# ATtiny84.net
KiCad netlist of a schematic drawn in EAGLE
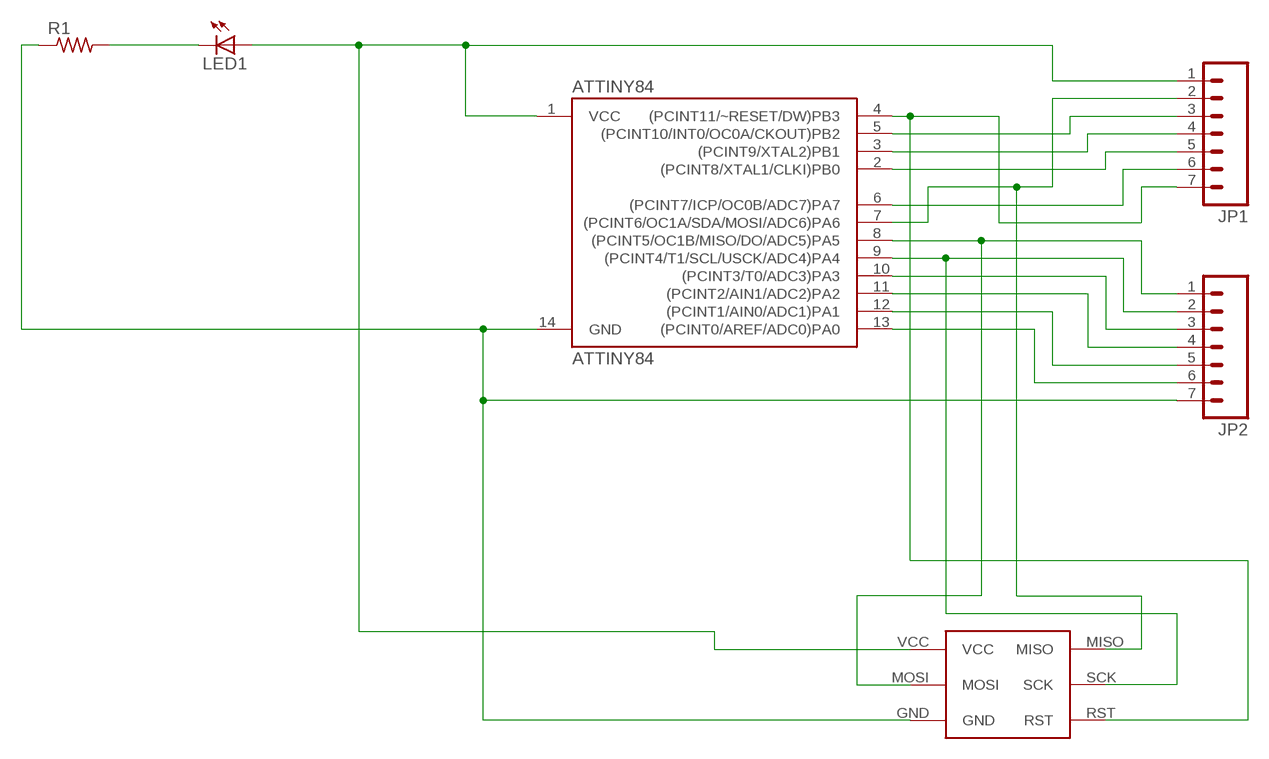
[diagram p0: schematic, sheet 1]

(export (version "E")
  (design (tool "Eeschema 10.0.6"))
  (components
    (comp (ref "ATTINY84")
      (value "ATTINY84")
      (footprint "eagle-import:SO14")
      (libsource (lib "eagle-import") (part "ATTINY84"))
    )
    (comp (ref "JP1")
      (value "M07")
      (footprint "eagle-import:1X07")
      (libsource (lib "eagle-import") (part "M07"))
    )
    (comp (ref "JP2")
      (value "M07")
      (footprint "eagle-import:1X07")
      (libsource (lib "eagle-import") (part "M07"))
    )
    (comp (ref "LED1")
      (value "LEDSML0603")
      (footprint "eagle-import:SML0603")
      (libsource (lib "eagle-import") (part "LEDSML0603"))
    )
    (comp (ref "R1")
      (value "R-US_R0805W")
      (footprint "eagle-import:R0805W")
      (libsource (lib "eagle-import") (part "R-US_R0805W"))
    )
    (comp (ref "U$2")
      (value "POGO_PIN_SPI_PAD")
      (footprint "eagle-import:POGO_PIN_SPI_PAD")
      (libsource (lib "eagle-import") (part "POGO_PIN_SPI_PAD"))
    )
  )
  (nets
    (net (code "1") (name "Net-(ATTINY84-(PCINT0{slash}AREF{slash}ADC0)PA0)") (class "Default")
      (node (ref "ATTINY84") (pin "13") (pinfunction "(PCINT0/AREF/ADC0)PA0_13") (pintype "bidirectional"))
      (node (ref "JP2") (pin "6") (pinfunction "6_6") (pintype "passive"))
    )
    (net (code "2") (name "Net-(ATTINY84-(PCINT1{slash}AIN0{slash}ADC1)PA1)") (class "Default")
      (node (ref "ATTINY84") (pin "12") (pinfunction "(PCINT1/AIN0/ADC1)PA1_12") (pintype "bidirectional"))
      (node (ref "JP2") (pin "5") (pinfunction "5_5") (pintype "passive"))
    )
    (net (code "3") (name "Net-(ATTINY84-(PCINT2{slash}AIN1{slash}ADC2)PA2)") (class "Default")
      (node (ref "ATTINY84") (pin "11") (pinfunction "(PCINT2/AIN1/ADC2)PA2_11") (pintype "bidirectional"))
      (node (ref "JP2") (pin "4") (pinfunction "4_4") (pintype "passive"))
    )
    (net (code "4") (name "Net-(ATTINY84-(PCINT3{slash}T0{slash}ADC3)PA3)") (class "Default")
      (node (ref "ATTINY84") (pin "10") (pinfunction "(PCINT3/T0/ADC3)PA3_10") (pintype "bidirectional"))
      (node (ref "JP2") (pin "3") (pinfunction "3_3") (pintype "passive"))
    )
    (net (code "5") (name "Net-(ATTINY84-(PCINT4{slash}T1{slash}SCL{slash}USCK{slash}ADC4)PA4)") (class "Default")
      (node (ref "ATTINY84") (pin "9") (pinfunction "(PCINT4/T1/SCL/USCK/ADC4)PA4_9") (pintype "bidirectional"))
      (node (ref "JP2") (pin "2") (pinfunction "2_2") (pintype "passive"))
      (node (ref "U$2") (pin "SCK") (pinfunction "SCK_SCK") (pintype "bidirectional"))
    )
    (net (code "6") (name "Net-(ATTINY84-(PCINT5{slash}OC1B{slash}MISO{slash}DO{slash}ADC5)PA5)") (class "Default")
      (node (ref "ATTINY84") (pin "8") (pinfunction "(PCINT5/OC1B/MISO/DO/ADC5)PA5_8") (pintype "bidirectional"))
      (node (ref "JP2") (pin "1") (pinfunction "1_1") (pintype "passive"))
      (node (ref "U$2") (pin "MOSI") (pinfunction "MOSI_MOSI") (pintype "bidirectional"))
    )
    (net (code "7") (name "Net-(ATTINY84-(PCINT6{slash}OC1A{slash}SDA{slash}MOSI{slash}ADC6)PA6)") (class "Default")
      (node (ref "ATTINY84") (pin "7") (pinfunction "(PCINT6/OC1A/SDA/MOSI/ADC6)PA6_7") (pintype "bidirectional"))
      (node (ref "JP1") (pin "2") (pinfunction "2_2") (pintype "passive"))
      (node (ref "U$2") (pin "MISO") (pinfunction "MISO_MISO") (pintype "bidirectional"))
    )
    (net (code "8") (name "Net-(ATTINY84-(PCINT7{slash}ICP{slash}OC0B{slash}ADC7)PA7)") (class "Default")
      (node (ref "ATTINY84") (pin "6") (pinfunction "(PCINT7/ICP/OC0B/ADC7)PA7_6") (pintype "bidirectional"))
      (node (ref "JP1") (pin "6") (pinfunction "6_6") (pintype "passive"))
    )
    (net (code "9") (name "Net-(ATTINY84-(PCINT8{slash}XTAL1{slash}CLKI)PB0)") (class "Default")
      (node (ref "ATTINY84") (pin "2") (pinfunction "(PCINT8/XTAL1/CLKI)PB0_2") (pintype "bidirectional"))
      (node (ref "JP1") (pin "5") (pinfunction "5_5") (pintype "passive"))
    )
    (net (code "10") (name "Net-(ATTINY84-(PCINT9{slash}XTAL2)PB1)") (class "Default")
      (node (ref "ATTINY84") (pin "3") (pinfunction "(PCINT9/XTAL2)PB1_3") (pintype "bidirectional"))
      (node (ref "JP1") (pin "4") (pinfunction "4_4") (pintype "passive"))
    )
    (net (code "11") (name "Net-(ATTINY84-(PCINT10{slash}INT0{slash}OC0A{slash}CKOUT)PB2)") (class "Default")
      (node (ref "ATTINY84") (pin "5") (pinfunction "(PCINT10/INT0/OC0A/CKOUT)PB2_5") (pintype "bidirectional"))
      (node (ref "JP1") (pin "3") (pinfunction "3_3") (pintype "passive"))
    )
    (net (code "12") (name "Net-(ATTINY84-(PCINT11{slash}~{RESET{slash}DW})PB3)") (class "Default")
      (node (ref "ATTINY84") (pin "4") (pinfunction "(PCINT11/~{RESET/DW})PB3_4") (pintype "bidirectional"))
      (node (ref "JP1") (pin "7") (pinfunction "7_7") (pintype "passive"))
      (node (ref "U$2") (pin "RST") (pinfunction "RST_RST") (pintype "bidirectional"))
    )
    (net (code "13") (name "Net-(ATTINY84-GND)") (class "Default")
      (node (ref "ATTINY84") (pin "14") (pinfunction "GND_14") (pintype "bidirectional"))
      (node (ref "JP2") (pin "7") (pinfunction "7_7") (pintype "passive"))
      (node (ref "R1") (pin "1") (pinfunction "1_1") (pintype "passive"))
      (node (ref "U$2") (pin "GND") (pinfunction "GND_GND") (pintype "bidirectional"))
    )
    (net (code "14") (name "Net-(ATTINY84-VCC)") (class "Default")
      (node (ref "ATTINY84") (pin "1") (pinfunction "VCC_1") (pintype "bidirectional"))
      (node (ref "JP1") (pin "1") (pinfunction "1_1") (pintype "passive"))
      (node (ref "LED1") (pin "A") (pinfunction "A_A") (pintype "passive"))
      (node (ref "U$2") (pin "VCC") (pinfunction "VCC_VCC") (pintype "bidirectional"))
    )
    (net (code "15") (name "Net-(LED1-PadC)") (class "Default")
      (node (ref "LED1") (pin "C") (pinfunction "C_C") (pintype "passive"))
      (node (ref "R1") (pin "2") (pinfunction "2_2") (pintype "passive"))
    )
  )
)
